# CAN.net
KiCad netlist of a schematic drawn in Altium Designer
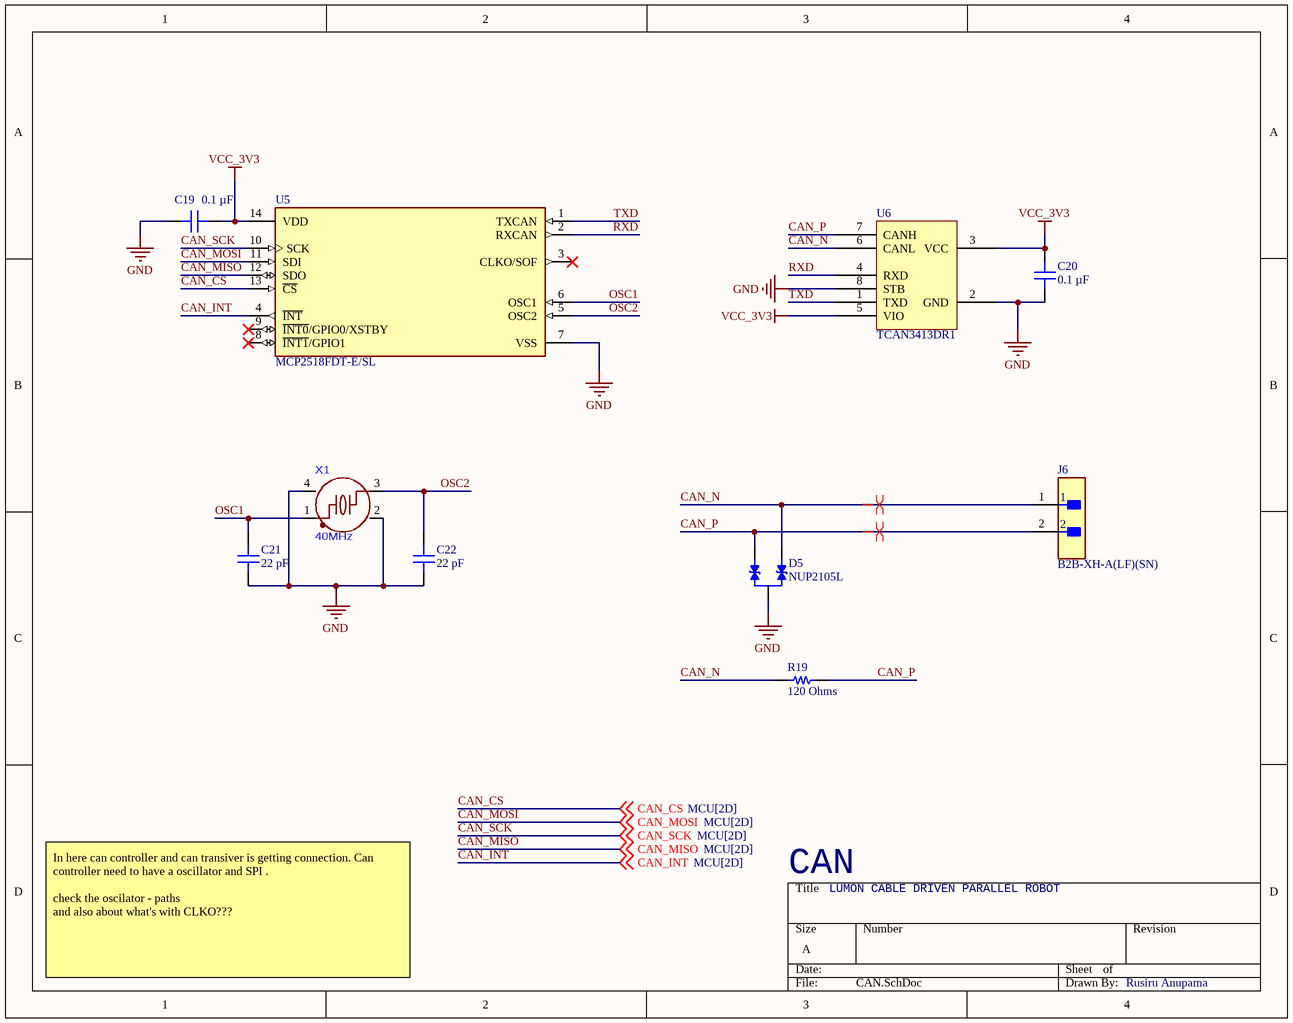
[diagram p0: CAN.SchDoc]

(export (version "E")
  (design (tool "Eeschema 10.0.6"))
  (components
    (comp (ref "C19")
      (value "0.1 µF")
      (footprint "CAP 0805_2012")
      (description "CAP CER 0.1UF 50V X7R 0805")
      (fields
        (field (name "PART NUMBER") "CC0805MRX7R9BB104")
        (field (name "CAPACITANCE") "0.1 µF")
        (field (name "MANUFACTURER") "Yageo")
      )
      (libsource (lib "Celestial Altium Library - altium_library") (part "Capacitor"))
    )
    (comp (ref "C20")
      (value "0.1 µF")
      (footprint "CAP 0805_2012")
      (description "CAP CER 0.1UF 50V X7R 0805")
      (fields
        (field (name "PART NUMBER") "CC0805MRX7R9BB104")
        (field (name "CAPACITANCE") "0.1 µF")
        (field (name "MANUFACTURER") "Yageo")
      )
      (libsource (lib "Celestial Altium Library - altium_library") (part "Capacitor"))
    )
    (comp (ref "C21")
      (value "22 pF")
      (footprint "CAP 0805_2012")
      (description "CAP CER 22PF 16V C0G/NP0 0805")
      (fields
        (field (name "PART NUMBER") "885012007012")
        (field (name "CAPACITANCE") "22 pF")
        (field (name "MANUFACTURER") "Würth Elektronik")
      )
      (libsource (lib "Celestial Altium Library - altium_library") (part "Capacitor"))
    )
    (comp (ref "C22")
      (value "22 pF")
      (footprint "CAP 0805_2012")
      (description "CAP CER 22PF 16V C0G/NP0 0805")
      (fields
        (field (name "PART NUMBER") "885012007012")
        (field (name "CAPACITANCE") "22 pF")
        (field (name "MANUFACTURER") "Würth Elektronik")
      )
      (libsource (lib "Celestial Altium Library - altium_library") (part "Capacitor"))
    )
    (comp (ref "D5")
      (value "NUP2105L")
      (footprint "SOT95P240X120-3N")
      (description "ESD, SOT-23, 0.1ÂµA, 24V, Unidir")
      (fields (field (name "MF") "Diotec Semiconductor") (field (name "LCSC PART #") "C14486"))
      (libsource (lib "Actuator Lib") (part "NUP2105L"))
    )
    (comp (ref "J6")
      (value "B2B-XH-A(LF)(SN)")
      (footprint "FP-B2B-XH-A_LF_SN-MFG")
      (description "CONN HEADER VERT 2POS 2.5MM")
      (fields (field (name "LCSC PART #") "C19271386"))
      (libsource (lib "Actuator Lib") (part "CMP-2000-05888-3"))
    )
    (comp (ref "R19")
      (value "120 Ohms")
      (footprint "RES 0805_2012")
      (description "RES SMD 120 OHM 1% 1/2W 0805")
      (fields (field (name "PART NUMBER") "CRCW0805120RFKEAHP") (field (name "MANUFACTURER") "Vishay Dale"))
      (libsource (lib "Celestial Altium Library - altium_library") (part "Resistor"))
    )
    (comp (ref "U5")
      (value "MCP2518FDT-E/SL")
      (footprint "FP-C04-065-SL-IPC_A")
      (description "IC CAN CONTROLLER SPI 14SOIC")
      (fields (field (name "LCSC PART #") "C626758"))
      (libsource (lib "Actuator Lib") (part "CMP-06298-000019-1"))
    )
    (comp (ref "U6")
      (value "TCAN3413DR1")
      (footprint "TCAN3413DR1")
      (fields (field (name "LCSC PART #") "C22396693"))
      (libsource (lib "Actuator Lib") (part "TCAN3413DR1"))
    )
    (comp (ref "X1")
      (value "40MHz")
      (footprint "CRYSTAL-SMD_4P-L3.2-W2.5-BL")
      (fields (field (name "LCSC PART #") "C5444549"))
      (libsource (lib "Actuator Lib") (part "XL2EL89CPI-111YLC-40M"))
    )
  )
  (nets
    (net (code "1") (name "/CAN_N") (class "Default")
      (node (ref "D5") (pin "1") (pinfunction "1_1") (pintype "passive"))
      (node (ref "J6") (pin "1") (pinfunction "1_1") (pintype "passive"))
      (node (ref "R19") (pin "1") (pinfunction "1_1") (pintype "passive"))
      (node (ref "U6") (pin "6") (pinfunction "CANL_6") (pintype "passive"))
    )
    (net (code "2") (name "/CAN_P") (class "Default")
      (node (ref "D5") (pin "2") (pinfunction "2_2") (pintype "passive"))
      (node (ref "J6") (pin "2") (pinfunction "2_2") (pintype "passive"))
      (node (ref "R19") (pin "2") (pinfunction "2_2") (pintype "passive"))
      (node (ref "U6") (pin "7") (pinfunction "CANH_7") (pintype "passive"))
    )
    (net (code "3") (name "/OSC1") (class "Default")
      (node (ref "C21") (pin "2") (pinfunction "2_2") (pintype "passive"))
      (node (ref "U5") (pin "6") (pinfunction "OSC1_6") (pintype "input"))
      (node (ref "X1") (pin "1") (pinfunction "1_1") (pintype "passive"))
    )
    (net (code "4") (name "/OSC2") (class "Default")
      (node (ref "C22") (pin "2") (pinfunction "2_2") (pintype "passive"))
      (node (ref "U5") (pin "5") (pinfunction "OSC2_5") (pintype "input"))
      (node (ref "X1") (pin "3") (pinfunction "3_3") (pintype "passive"))
    )
    (net (code "5") (name "/RXD") (class "Default")
      (node (ref "U5") (pin "2") (pinfunction "RXCAN_2") (pintype "output"))
      (node (ref "U6") (pin "4") (pinfunction "RXD_4") (pintype "passive"))
    )
    (net (code "6") (name "/TXD") (class "Default")
      (node (ref "U5") (pin "1") (pinfunction "TXCAN_1") (pintype "input"))
      (node (ref "U6") (pin "1") (pinfunction "TXD_1") (pintype "passive"))
    )
    (net (code "7") (name "CAN_CS") (class "Default")
      (node (ref "U5") (pin "13") (pinfunction "~{CS}_13") (pintype "input"))
    )
    (net (code "8") (name "CAN_INT") (class "Default")
      (node (ref "U5") (pin "4") (pinfunction "~{INT}_4") (pintype "output"))
    )
    (net (code "9") (name "CAN_MISO") (class "Default")
      (node (ref "U5") (pin "12") (pinfunction "SDO_12") (pintype "bidirectional"))
    )
    (net (code "10") (name "CAN_MOSI") (class "Default")
      (node (ref "U5") (pin "11") (pinfunction "SDI_11") (pintype "input"))
    )
    (net (code "11") (name "CAN_SCK") (class "Default")
      (node (ref "U5") (pin "10") (pinfunction "SCK_10") (pintype "input"))
    )
    (net (code "12") (name "GND") (class "Default")
      (node (ref "C19") (pin "1") (pinfunction "1_1") (pintype "passive"))
      (node (ref "C20") (pin "1") (pinfunction "1_1") (pintype "passive"))
      (node (ref "C21") (pin "1") (pinfunction "1_1") (pintype "passive"))
      (node (ref "C22") (pin "1") (pinfunction "1_1") (pintype "passive"))
      (node (ref "D5") (pin "3") (pinfunction "3_3") (pintype "passive"))
      (node (ref "U5") (pin "7") (pinfunction "VSS_7") (pintype "power_in"))
      (node (ref "U6") (pin "2") (pinfunction "GND_2") (pintype "passive"))
      (node (ref "U6") (pin "8") (pinfunction "STB_8") (pintype "passive"))
      (node (ref "X1") (pin "2") (pinfunction "GND_2") (pintype "passive"))
      (node (ref "X1") (pin "4") (pinfunction "GND_4") (pintype "passive"))
    )
    (net (code "13") (name "VCC_3V3") (class "Default")
      (node (ref "C19") (pin "2") (pinfunction "2_2") (pintype "passive"))
      (node (ref "C20") (pin "2") (pinfunction "2_2") (pintype "passive"))
      (node (ref "U5") (pin "14") (pinfunction "VDD_14") (pintype "power_in"))
      (node (ref "U6") (pin "3") (pinfunction "VCC_3") (pintype "passive"))
      (node (ref "U6") (pin "5") (pinfunction "VIO_5") (pintype "passive"))
    )
    (net (code "14") (name "unconnected-(U5-CLKO{slash}SOF-Pad3)") (class "Default")
      (node (ref "U5") (pin "3") (pinfunction "CLKO/SOF_3") (pintype "output+no_connect"))
    )
    (net (code "15") (name "unconnected-(U5-~{INT0}{slash}GPIO0{slash}XSTBY-Pad9)") (class "Default")
      (node (ref "U5") (pin "9") (pinfunction "~{INT0}/GPIO0/XSTBY_9") (pintype "bidirectional+no_connect"))
    )
    (net (code "16") (name "unconnected-(U5-~{INT1}{slash}GPIO1-Pad8)") (class "Default")
      (node (ref "U5") (pin "8") (pinfunction "~{INT1}/GPIO1_8") (pintype "bidirectional+no_connect"))
    )
  )
)
